# 01-Power.net
KiCad netlist of a schematic drawn in Altium Designer
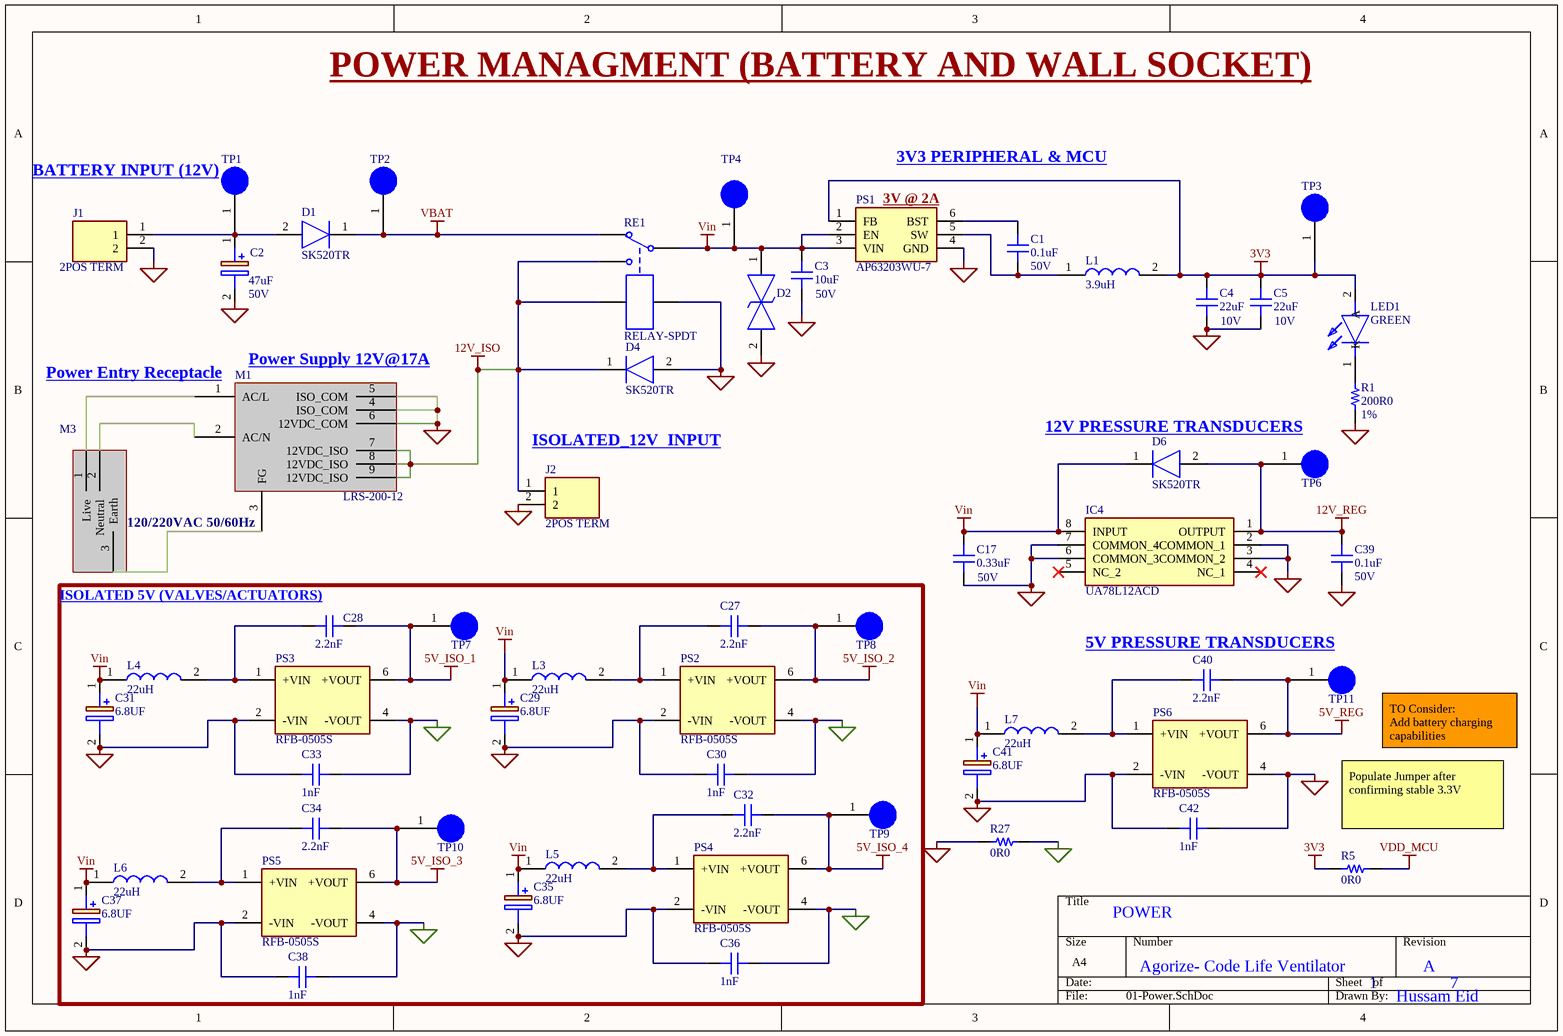
[diagram p0: 01-Power.SchDoc]

(export (version "E")
  (design (tool "Eeschema 10.0.6"))
  (components
    (comp (ref "C1")
      (value "0.1uF")
      (footprint "CAP 0603/1608")
      (description "CAP CER 0.1UF 50V X7R 0603")
      (fields (field (name "TOLERANCE") "20%") (field (name "VOLTAGE RATING") "50V"))
      (libsource (lib "Celestial Library Database") (part "Capacitor"))
    )
    (comp (ref "C2")
      (value "47uF")
      (footprint "SamacSys:EEE1HA470XP")
      (description "CAP ALUM 47UF 20% 50V SMD")
      (fields
        (field (name "TOLERANCE") "20%")
        (field (name "VOLTAGE RATING") "50V")
        (field (name "VOLTAGE") "50V")
      )
      (libsource (lib "*") (part "EEE-1HA470XP"))
    )
    (comp (ref "C3")
      (value "10uF")
      (footprint "CAP 1206/3216")
      (description "CAP CER 10UF 25V X7R 1206")
      (fields (field (name "TOLERANCE") "20%") (field (name "VOLTAGE RATING") "50V"))
      (libsource (lib "Celestial Library Database") (part "Capacitor"))
    )
    (comp (ref "C4")
      (value "22uF")
      (footprint "RES 0805/2012")
      (description "CAP CER 22UF 10V X5R 0805")
      (fields (field (name "VOLTAGE") "10V") (field (name "TOLERANCE") "20%"))
      (libsource (lib "Celestial Library Database") (part "Capacitor"))
    )
    (comp (ref "C5")
      (value "22uF")
      (footprint "RES 0805/2012")
      (description "CAP CER 22UF 10V X5R 0805")
      (fields (field (name "VOLTAGE") "10V") (field (name "TOLERANCE") "20%"))
      (libsource (lib "Celestial Library Database") (part "Capacitor"))
    )
    (comp (ref "C17")
      (value "0.33uF")
      (footprint "CAP 0603/1608")
      (description "CAP CER 0.33UF 50V X5R 0603")
      (fields (field (name "VOLTAGE RATING") "50V") (field (name "TOLERANCE") "10%"))
      (libsource (lib "Celestial Library Database") (part "Capacitor"))
    )
    (comp (ref "C27")
      (value "2.2nF")
      (footprint "CAP 0603/1608")
      (description "CAP CER 2.2nF 50V X7R 0603")
      (fields (field (name "TOLERANCE") "20%"))
      (libsource (lib "Celestial Library Database") (part "Capacitor"))
    )
    (comp (ref "C28")
      (value "2.2nF")
      (footprint "CAP 0603/1608")
      (description "CAP CER 2.2nF 50V X7R 0603")
      (fields (field (name "TOLERANCE") "20%"))
      (libsource (lib "Celestial Library Database") (part "Capacitor"))
    )
    (comp (ref "C29")
      (value "6.8UF")
      (footprint "CAPAE430X550N")
      (description "CAP 6.8 UF 20% 50 V")
      (fields (field (name "TOLERANCE") "20%"))
      (libsource (lib "Schlib1") (part "CAP_ELECTROLYTIC"))
    )
    (comp (ref "C30")
      (value "1nF")
      (footprint "CAP 0603/1608")
      (description "CAP CER 1nF 50V X7R 0603")
      (fields (field (name "TOLERANCE") "20%"))
      (libsource (lib "Celestial Library Database") (part "Capacitor"))
    )
    (comp (ref "C31")
      (value "6.8UF")
      (footprint "CAPAE430X550N")
      (description "CAP 6.8 UF 20% 50 V")
      (fields (field (name "TOLERANCE") "20%"))
      (libsource (lib "Schlib1") (part "CAP_ELECTROLYTIC"))
    )
    (comp (ref "C32")
      (value "2.2nF")
      (footprint "CAP 0603/1608")
      (description "CAP CER 2.2nF 50V X7R 0603")
      (fields (field (name "TOLERANCE") "20%"))
      (libsource (lib "Celestial Library Database") (part "Capacitor"))
    )
    (comp (ref "C33")
      (value "1nF")
      (footprint "CAP 0603/1608")
      (description "CAP CER 1nF 50V X7R 0603")
      (fields (field (name "TOLERANCE") "20%"))
      (libsource (lib "Celestial Library Database") (part "Capacitor"))
    )
    (comp (ref "C34")
      (value "2.2nF")
      (footprint "CAP 0603/1608")
      (description "CAP CER 2.2nF 50V X7R 0603")
      (fields (field (name "TOLERANCE") "20%"))
      (libsource (lib "Celestial Library Database") (part "Capacitor"))
    )
    (comp (ref "C35")
      (value "6.8UF")
      (footprint "CAPAE430X550N")
      (description "CAP 6.8 UF 20% 50 V")
      (fields (field (name "TOLERANCE") "20%"))
      (libsource (lib "Schlib1") (part "CAP_ELECTROLYTIC"))
    )
    (comp (ref "C36")
      (value "1nF")
      (footprint "CAP 0603/1608")
      (description "CAP CER 1nF 50V X7R 0603")
      (fields (field (name "TOLERANCE") "20%"))
      (libsource (lib "Celestial Library Database") (part "Capacitor"))
    )
    (comp (ref "C37")
      (value "6.8UF")
      (footprint "CAPAE430X550N")
      (description "CAP 6.8 UF 20% 50 V")
      (fields (field (name "TOLERANCE") "20%"))
      (libsource (lib "Schlib1") (part "CAP_ELECTROLYTIC"))
    )
    (comp (ref "C38")
      (value "1nF")
      (footprint "CAP 0603/1608")
      (description "CAP CER 1nF 50V X7R 0603")
      (fields (field (name "TOLERANCE") "20%"))
      (libsource (lib "Celestial Library Database") (part "Capacitor"))
    )
    (comp (ref "C39")
      (value "0.1uF")
      (footprint "CAP 0603/1608")
      (description "CAP CER 0.1UF 50V X7R 0603")
      (fields (field (name "TOLERANCE") "20%") (field (name "VOLTAGE RATING") "50V"))
      (libsource (lib "Celestial Library Database") (part "Capacitor"))
    )
    (comp (ref "C40")
      (value "2.2nF")
      (footprint "CAP 0603/1608")
      (description "CAP CER 2.2nF 50V X7R 0603")
      (fields (field (name "TOLERANCE") "20%"))
      (libsource (lib "Celestial Library Database") (part "Capacitor"))
    )
    (comp (ref "C41")
      (value "6.8UF")
      (footprint "CAPAE430X550N")
      (description "CAP 6.8 UF 20% 50 V")
      (fields (field (name "TOLERANCE") "20%"))
      (libsource (lib "Schlib1") (part "CAP_ELECTROLYTIC"))
    )
    (comp (ref "C42")
      (value "1nF")
      (footprint "CAP 0603/1608")
      (description "CAP CER 1nF 50V X7R 0603")
      (fields (field (name "TOLERANCE") "20%"))
      (libsource (lib "Celestial Library Database") (part "Capacitor"))
    )
    (comp (ref "D1")
      (value "SK520TR")
      (footprint "SamacSys:DIOM8060X295N")
      (description "DIODE SCHOTTKY 200V 5A SMC")
      (libsource (lib "*") (part "SK520TR"))
    )
    (comp (ref "D2")
      (value "DF2B26M4SL,L3F")
      (footprint "PcbLib1:TVS")
      (description "BI-DIRECTIONAL ESD PROTECTION DI")
      (libsource (lib "*") (part "1KSMB12CA"))
    )
    (comp (ref "D4")
      (value "SK520TR")
      (footprint "SamacSys:DIOM8060X295N")
      (description "DIODE SCHOTTKY 200V 5A SMC")
      (libsource (lib "*") (part "SK520TR"))
    )
    (comp (ref "D6")
      (value "SK520TR")
      (footprint "SamacSys:DIOM8060X295N")
      (description "DIODE SCHOTTKY 200V 5A SMC")
      (libsource (lib "*") (part "SK520TR"))
    )
    (comp (ref "IC4")
      (value "UA78L12ACD")
      (footprint "SamacSys:SOIC127P600X175-8N")
      (description "Linear Voltage Regulator IC  1 Output  100mA 8-SOIC")
      (fields (field (name "MOUSER PART NUMBER") "595-UA78L12ACD") (field (name "RS PART NUMBER") "6616727P"))
      (libsource (lib "*") (part "UA78L12ACD"))
    )
    (comp (ref "J1")
      (value "2POS TERM")
      (footprint "PcbLib1:SHDR2W110P0X500_1X2_1000X830X1140P")
      (description "TERM BLK 2POS SIDE ENTRY 5MM PCB")
      (fields (field (name "VOLTAGE") "300V"))
      (libsource (lib "*") (part "1935161"))
    )
    (comp (ref "J2")
      (value "2POS TERM")
      (footprint "PcbLib1:SHDR2W110P0X500_1X2_1000X830X1140P")
      (description "TERM BLK 2POS SIDE ENTRY 5MM PCB")
      (fields (field (name "VOLTAGE") "300V"))
      (libsource (lib "") (part "1935161_1"))
    )
    (comp (ref "L1")
      (value "3.9uH")
      (footprint "SamacSys:1255AY100MP3")
      (description "3.9µH Shielded Wirewound Inductor 4.2A 26.4mOhm Max Nonstandard")
      (fields (field (name "TOLERANCE") "30%"))
      (libsource (lib "*") (part "1255AY-3R9N=P3"))
    )
    (comp (ref "L3")
      (value "22uH")
      (footprint "SamacSys:1255AY100MP3")
      (description "Inductor Unshielded Wirewound  190mA 4.81Ohm Max 0805 (2012 Metric)")
      (fields (field (name "TOLERANCE") "20%"))
      (libsource (lib "*") (part "1255AY-3R9N=P3"))
    )
    (comp (ref "L4")
      (value "22uH")
      (footprint "SamacSys:1255AY100MP3")
      (description "Inductor Unshielded Wirewound  190mA 4.81Ohm Max 0805 (2012 Metric)")
      (fields (field (name "TOLERANCE") "20%"))
      (libsource (lib "*") (part "1255AY-3R9N=P3"))
    )
    (comp (ref "L5")
      (value "22uH")
      (footprint "SamacSys:1255AY100MP3")
      (description "Inductor Unshielded Wirewound  190mA 4.81Ohm Max 0805 (2012 Metric)")
      (fields (field (name "TOLERANCE") "20%"))
      (libsource (lib "*") (part "1255AY-3R9N=P3"))
    )
    (comp (ref "L6")
      (value "22uH")
      (footprint "SamacSys:1255AY100MP3")
      (description "Inductor Unshielded Wirewound  190mA 4.81Ohm Max 0805 (2012 Metric)")
      (fields (field (name "TOLERANCE") "20%"))
      (libsource (lib "*") (part "1255AY-3R9N=P3"))
    )
    (comp (ref "L7")
      (value "22uH")
      (footprint "SamacSys:1255AY100MP3")
      (description "Inductor Unshielded Wirewound  190mA 4.81Ohm Max 0805 (2012 Metric)")
      (fields (field (name "TOLERANCE") "20%"))
      (libsource (lib "*") (part "1255AY-3R9N=P3"))
    )
    (comp (ref "LED1")
      (value "GREEN")
      (footprint "SamacSys:150060GS73220")
      (description "LED GREEN CLEAR 0603 SMD")
      (libsource (lib "*") (part "150060GS73220"))
    )
    (comp (ref "M1")
      (value "12V 204W PS")
      (description "Enclosed AC DC Converters 1 Output 12V    17A 90 ~ 132 VAC, 180 ~ 264 VAC, 240 ~ 370 VDC Input")
      (fields (field (name "MANUFACTURER PART NUMBER 1") "LRS-200-12"))
      (libsource (lib "Schlib1") (part "12V 204W PS"))
    )
    (comp (ref "M3")
      (value "Power Entry Receptacle")
      (description "Power Entry Connector Receptacle, Male Blades IEC 320-C14 Panel Mount, Flange")
      (libsource (lib "Schlib1") (part "Power Entry Receptacle"))
    )
    (comp (ref "PS1")
      (value "AP63203WU-7")
      (footprint "SamacSys:SOT95P280X100-6N")
      (description "IC REG BUCK 3.3V 2A TSOT26")
      (libsource (lib "*") (part "AP63203WU-7"))
    )
    (comp (ref "PS2")
      (value "RFB-0505S")
      (footprint "SamacSys:RFB0505S")
      (description "DC DC CONVERTER 5V 1W")
      (fields (field (name "MOUSER PART NUMBER") "919-RFB-0505S") (field (name "RS PART NUMBER") "1855539P"))
      (libsource (lib "Schlib1") (part "RFB-0505S"))
    )
    (comp (ref "PS3")
      (value "RFB-0505S")
      (footprint "SamacSys:RFB0505S")
      (description "DC DC CONVERTER 5V 1W")
      (fields (field (name "MOUSER PART NUMBER") "919-RFB-0505S") (field (name "RS PART NUMBER") "1855539P"))
      (libsource (lib "Schlib1") (part "RFB-0505S"))
    )
    (comp (ref "PS4")
      (value "RFB-0505S")
      (footprint "SamacSys:RFB0505S")
      (description "DC DC CONVERTER 5V 1W")
      (fields (field (name "MOUSER PART NUMBER") "919-RFB-0505S") (field (name "RS PART NUMBER") "1855539P"))
      (libsource (lib "Schlib1") (part "RFB-0505S"))
    )
    (comp (ref "PS5")
      (value "RFB-0505S")
      (footprint "SamacSys:RFB0505S")
      (description "DC DC CONVERTER 5V 1W")
      (fields (field (name "MOUSER PART NUMBER") "919-RFB-0505S") (field (name "RS PART NUMBER") "1855539P"))
      (libsource (lib "Schlib1") (part "RFB-0505S"))
    )
    (comp (ref "PS6")
      (value "RFB-0505S")
      (footprint "SamacSys:RFB0505S")
      (description "DC DC CONVERTER 5V 1W")
      (fields (field (name "MOUSER PART NUMBER") "919-RFB-0505S") (field (name "RS PART NUMBER") "1855539P"))
      (libsource (lib "Schlib1") (part "RFB-0505S"))
    )
    (comp (ref "R1")
      (value "200R0")
      (footprint "RES 1206/3216")
      (description "RES SMD 10K OHM 1% 1/4W 1206")
      (fields (field (name "TOLERANCE") "1%"))
      (libsource (lib "Celestial Library Database") (part "Resistor"))
    )
    (comp (ref "R5")
      (value "0R0")
      (footprint "RES 0603/1608")
      (description "RES SMD 0 OHM JUMPER 1/10W 0603")
      (fields (field (name "TOLERANCE") "0%"))
      (libsource (lib "Celestial Library Database") (part "Resistor"))
    )
    (comp (ref "R27")
      (value "0R0")
      (footprint "RES 0603/1608")
      (description "RES SMD 0 OHM JUMPER 1/10W 0603")
      (fields (field (name "TOLERANCE") "0%"))
      (libsource (lib "Celestial Library Database") (part "Resistor"))
    )
    (comp (ref "RE1")
      (value "RELAY-SPDT")
      (footprint "T9GV5L145")
      (description "RELAY GEN PURPOSE SPDT 20A 12V")
      (libsource (lib "Schlib1") (part "RELAY-SPDT"))
    )
    (comp (ref "TP1")
      (value "TP")
      (footprint "TP")
      (description "Test Point")
      (libsource (lib "Schlib1") (part "TP"))
    )
    (comp (ref "TP2")
      (value "TP")
      (footprint "TP")
      (description "Test Point")
      (libsource (lib "Schlib1") (part "TP"))
    )
    (comp (ref "TP3")
      (value "TP")
      (footprint "TP")
      (description "Test Point")
      (libsource (lib "Schlib1") (part "TP"))
    )
    (comp (ref "TP4")
      (value "TP")
      (footprint "TP")
      (description "Test Point")
      (libsource (lib "Schlib1") (part "TP"))
    )
    (comp (ref "TP6")
      (value "TP")
      (footprint "TP")
      (description "Test Point")
      (libsource (lib "Schlib1") (part "TP"))
    )
    (comp (ref "TP7")
      (value "TP")
      (footprint "TP")
      (description "Test Point")
      (libsource (lib "Schlib1") (part "TP"))
    )
    (comp (ref "TP8")
      (value "TP")
      (footprint "TP")
      (description "Test Point")
      (libsource (lib "Schlib1") (part "TP"))
    )
    (comp (ref "TP9")
      (value "TP")
      (footprint "TP")
      (description "Test Point")
      (libsource (lib "Schlib1") (part "TP"))
    )
    (comp (ref "TP10")
      (value "TP")
      (footprint "TP")
      (description "Test Point")
      (libsource (lib "Schlib1") (part "TP"))
    )
    (comp (ref "TP11")
      (value "TP")
      (footprint "TP")
      (description "Test Point")
      (libsource (lib "Schlib1") (part "TP"))
    )
  )
  (nets
    (net (code "1") (name "3V3") (class "Default")
      (node (ref "C4") (pin "2") (pinfunction "2_2") (pintype "passive"))
      (node (ref "C5") (pin "2") (pinfunction "2_2") (pintype "passive"))
      (node (ref "L1") (pin "2") (pinfunction "2_2") (pintype "passive"))
      (node (ref "LED1") (pin "2") (pinfunction "A_2") (pintype "passive"))
      (node (ref "PS1") (pin "1") (pinfunction "FB_1") (pintype "passive"))
      (node (ref "R5") (pin "1") (pinfunction "1_1") (pintype "passive"))
      (node (ref "TP3") (pin "1") (pinfunction "1_1") (pintype "passive"))
    )
    (net (code "2") (name "5V_ISO_1") (class "Default")
      (node (ref "C28") (pin "2") (pinfunction "2_2") (pintype "passive"))
      (node (ref "PS3") (pin "6") (pinfunction "+VOUT_6") (pintype "passive"))
      (node (ref "TP7") (pin "1") (pinfunction "1_1") (pintype "passive"))
    )
    (net (code "3") (name "5V_ISO_2") (class "Default")
      (node (ref "C27") (pin "2") (pinfunction "2_2") (pintype "passive"))
      (node (ref "PS2") (pin "6") (pinfunction "+VOUT_6") (pintype "passive"))
      (node (ref "TP8") (pin "1") (pinfunction "1_1") (pintype "passive"))
    )
    (net (code "4") (name "5V_ISO_3") (class "Default")
      (node (ref "C34") (pin "2") (pinfunction "2_2") (pintype "passive"))
      (node (ref "PS5") (pin "6") (pinfunction "+VOUT_6") (pintype "passive"))
      (node (ref "TP10") (pin "1") (pinfunction "1_1") (pintype "passive"))
    )
    (net (code "5") (name "5V_ISO_4") (class "Default")
      (node (ref "C32") (pin "2") (pinfunction "2_2") (pintype "passive"))
      (node (ref "PS4") (pin "6") (pinfunction "+VOUT_6") (pintype "passive"))
      (node (ref "TP9") (pin "1") (pinfunction "1_1") (pintype "passive"))
    )
    (net (code "6") (name "5V_REG") (class "Default")
      (node (ref "C40") (pin "2") (pinfunction "2_2") (pintype "passive"))
      (node (ref "PS6") (pin "6") (pinfunction "+VOUT_6") (pintype "passive"))
      (node (ref "TP11") (pin "1") (pinfunction "1_1") (pintype "passive"))
    )
    (net (code "7") (name "12V_ISO") (class "Default")
      (node (ref "D4") (pin "1") (pinfunction "K_1") (pintype "passive"))
      (node (ref "J2") (pin "1") (pinfunction "1_1") (pintype "passive"))
      (node (ref "M1") (pin "7") (pinfunction "12VDC_ISO_7") (pintype "passive"))
      (node (ref "M1") (pin "8") (pinfunction "12VDC_ISO_8") (pintype "passive"))
      (node (ref "M1") (pin "9") (pinfunction "12VDC_ISO_9") (pintype "passive"))
      (node (ref "RE1") (pin "3") (pinfunction "3_3") (pintype "passive"))
      (node (ref "RE1") (pin "4") (pinfunction "4_4") (pintype "passive"))
    )
    (net (code "8") (name "12V_REG") (class "Default")
      (node (ref "C39") (pin "1") (pinfunction "1_1") (pintype "passive"))
      (node (ref "D6") (pin "2") (pinfunction "A_2") (pintype "passive"))
      (node (ref "IC4") (pin "1") (pinfunction "OUTPUT_1") (pintype "passive"))
      (node (ref "TP6") (pin "1") (pinfunction "1_1") (pintype "passive"))
    )
    (net (code "9") (name "COM") (class "Default")
      (node (ref "C17") (pin "2") (pinfunction "2_2") (pintype "passive"))
      (node (ref "C2") (pin "2") (pinfunction "-_2") (pintype "passive"))
      (node (ref "C29") (pin "2") (pinfunction "-_2") (pintype "passive"))
      (node (ref "C3") (pin "1") (pinfunction "1_1") (pintype "passive"))
      (node (ref "C30") (pin "1") (pinfunction "1_1") (pintype "passive"))
      (node (ref "C31") (pin "2") (pinfunction "-_2") (pintype "passive"))
      (node (ref "C33") (pin "1") (pinfunction "1_1") (pintype "passive"))
      (node (ref "C35") (pin "2") (pinfunction "-_2") (pintype "passive"))
      (node (ref "C36") (pin "1") (pinfunction "1_1") (pintype "passive"))
      (node (ref "C37") (pin "2") (pinfunction "-_2") (pintype "passive"))
      (node (ref "C38") (pin "1") (pinfunction "1_1") (pintype "passive"))
      (node (ref "C39") (pin "2") (pinfunction "2_2") (pintype "passive"))
      (node (ref "C4") (pin "1") (pinfunction "1_1") (pintype "passive"))
      (node (ref "C41") (pin "2") (pinfunction "-_2") (pintype "passive"))
      (node (ref "C42") (pin "1") (pinfunction "1_1") (pintype "passive"))
      (node (ref "C42") (pin "2") (pinfunction "2_2") (pintype "passive"))
      (node (ref "C5") (pin "1") (pinfunction "1_1") (pintype "passive"))
      (node (ref "D2") (pin "2") (pinfunction "2_2") (pintype "passive"))
      (node (ref "D4") (pin "2") (pinfunction "A_2") (pintype "passive"))
      (node (ref "IC4") (pin "2") (pinfunction "COMMON_1_2") (pintype "passive"))
      (node (ref "IC4") (pin "3") (pinfunction "COMMON_2_3") (pintype "passive"))
      (node (ref "IC4") (pin "6") (pinfunction "COMMON_3_6") (pintype "passive"))
      (node (ref "IC4") (pin "7") (pinfunction "COMMON_4_7") (pintype "passive"))
      (node (ref "J1") (pin "2") (pinfunction "2_2") (pintype "passive"))
      (node (ref "J2") (pin "2") (pinfunction "2_2") (pintype "passive"))
      (node (ref "M1") (pin "4") (pinfunction "ISO_COM_4") (pintype "passive"))
      (node (ref "M1") (pin "5") (pinfunction "ISO_COM_5") (pintype "passive"))
      (node (ref "M1") (pin "6") (pinfunction "12VDC_COM_6") (pintype "passive"))
      (node (ref "PS1") (pin "4") (pinfunction "GND_4") (pintype "power_in"))
      (node (ref "PS2") (pin "2") (pinfunction "-VIN_2") (pintype "passive"))
      (node (ref "PS3") (pin "2") (pinfunction "-VIN_2") (pintype "passive"))
      (node (ref "PS4") (pin "2") (pinfunction "-VIN_2") (pintype "passive"))
      (node (ref "PS5") (pin "2") (pinfunction "-VIN_2") (pintype "passive"))
      (node (ref "PS6") (pin "2") (pinfunction "-VIN_2") (pintype "passive"))
      (node (ref "PS6") (pin "4") (pinfunction "-VOUT_4") (pintype "passive"))
      (node (ref "R1") (pin "1") (pinfunction "1_1") (pintype "passive"))
      (node (ref "R27") (pin "1") (pinfunction "1_1") (pintype "passive"))
      (node (ref "RE1") (pin "2") (pinfunction "2_2") (pintype "passive"))
    )
    (net (code "10") (name "COM_ISO") (class "Default")
      (node (ref "C30") (pin "2") (pinfunction "2_2") (pintype "passive"))
      (node (ref "C33") (pin "2") (pinfunction "2_2") (pintype "passive"))
      (node (ref "C36") (pin "2") (pinfunction "2_2") (pintype "passive"))
      (node (ref "C38") (pin "2") (pinfunction "2_2") (pintype "passive"))
      (node (ref "PS2") (pin "4") (pinfunction "-VOUT_4") (pintype "passive"))
      (node (ref "PS3") (pin "4") (pinfunction "-VOUT_4") (pintype "passive"))
      (node (ref "PS4") (pin "4") (pinfunction "-VOUT_4") (pintype "passive"))
      (node (ref "PS5") (pin "4") (pinfunction "-VOUT_4") (pintype "passive"))
      (node (ref "R27") (pin "2") (pinfunction "2_2") (pintype "passive"))
    )
    (net (code "11") (name "Net-(C2-+)") (class "Default")
      (node (ref "C2") (pin "1") (pinfunction "+_1") (pintype "passive"))
      (node (ref "D1") (pin "2") (pinfunction "A_2") (pintype "passive"))
      (node (ref "J1") (pin "1") (pinfunction "1_1") (pintype "passive"))
      (node (ref "TP1") (pin "1") (pinfunction "1_1") (pintype "passive"))
    )
    (net (code "12") (name "Net-(LED1-K)") (class "Default")
      (node (ref "LED1") (pin "1") (pinfunction "K_1") (pintype "passive"))
      (node (ref "R1") (pin "2") (pinfunction "2_2") (pintype "passive"))
    )
    (net (code "13") (name "Net-(M1-AC{slash}L)") (class "Default")
      (node (ref "M1") (pin "1") (pinfunction "AC/L_1") (pintype "passive"))
      (node (ref "M3") (pin "1") (pinfunction "Live_1") (pintype "passive"))
    )
    (net (code "14") (name "Net-(M1-AC{slash}N)") (class "Default")
      (node (ref "M1") (pin "2") (pinfunction "AC/N_2") (pintype "passive"))
      (node (ref "M3") (pin "2") (pinfunction "Neutral_2") (pintype "passive"))
    )
    (net (code "15") (name "Net-(M1-FG)") (class "Default")
      (node (ref "M1") (pin "3") (pinfunction "FG_3") (pintype "passive"))
      (node (ref "M3") (pin "3") (pinfunction "Earth_3") (pintype "passive"))
    )
    (net (code "16") (name "Net-(PS1-BST)") (class "Default")
      (node (ref "C1") (pin "1") (pinfunction "1_1") (pintype "passive"))
      (node (ref "PS1") (pin "6") (pinfunction "BST_6") (pintype "passive"))
    )
    (net (code "17") (name "Net-(PS1-SW)") (class "Default")
      (node (ref "C1") (pin "2") (pinfunction "2_2") (pintype "passive"))
      (node (ref "L1") (pin "1") (pinfunction "1_1") (pintype "passive"))
      (node (ref "PS1") (pin "5") (pinfunction "SW_5") (pintype "passive"))
    )
    (net (code "18") (name "Net-(PS2-+VIN)") (class "Default")
      (node (ref "C27") (pin "1") (pinfunction "1_1") (pintype "passive"))
      (node (ref "L3") (pin "2") (pinfunction "2_2") (pintype "passive"))
      (node (ref "PS2") (pin "1") (pinfunction "+VIN_1") (pintype "passive"))
    )
    (net (code "19") (name "Net-(PS3-+VIN)") (class "Default")
      (node (ref "C28") (pin "1") (pinfunction "1_1") (pintype "passive"))
      (node (ref "L4") (pin "2") (pinfunction "2_2") (pintype "passive"))
      (node (ref "PS3") (pin "1") (pinfunction "+VIN_1") (pintype "passive"))
    )
    (net (code "20") (name "Net-(PS4-+VIN)") (class "Default")
      (node (ref "C32") (pin "1") (pinfunction "1_1") (pintype "passive"))
      (node (ref "L5") (pin "2") (pinfunction "2_2") (pintype "passive"))
      (node (ref "PS4") (pin "1") (pinfunction "+VIN_1") (pintype "passive"))
    )
    (net (code "21") (name "Net-(PS5-+VIN)") (class "Default")
      (node (ref "C34") (pin "1") (pinfunction "1_1") (pintype "passive"))
      (node (ref "L6") (pin "2") (pinfunction "2_2") (pintype "passive"))
      (node (ref "PS5") (pin "1") (pinfunction "+VIN_1") (pintype "passive"))
    )
    (net (code "22") (name "Net-(PS6-+VIN)") (class "Default")
      (node (ref "C40") (pin "1") (pinfunction "1_1") (pintype "passive"))
      (node (ref "L7") (pin "2") (pinfunction "2_2") (pintype "passive"))
      (node (ref "PS6") (pin "1") (pinfunction "+VIN_1") (pintype "passive"))
    )
    (net (code "23") (name "VBAT") (class "Default")
      (node (ref "D1") (pin "1") (pinfunction "K_1") (pintype "passive"))
      (node (ref "RE1") (pin "5") (pinfunction "5_5") (pintype "passive"))
      (node (ref "TP2") (pin "1") (pinfunction "1_1") (pintype "passive"))
    )
    (net (code "24") (name "VDD_MCU") (class "Default")
      (node (ref "R5") (pin "2") (pinfunction "2_2") (pintype "passive"))
    )
    (net (code "25") (name "Vin") (class "Default")
      (node (ref "C17") (pin "1") (pinfunction "1_1") (pintype "passive"))
      (node (ref "C29") (pin "1") (pinfunction "+_1") (pintype "passive"))
      (node (ref "C3") (pin "2") (pinfunction "2_2") (pintype "passive"))
      (node (ref "C31") (pin "1") (pinfunction "+_1") (pintype "passive"))
      (node (ref "C35") (pin "1") (pinfunction "+_1") (pintype "passive"))
      (node (ref "C37") (pin "1") (pinfunction "+_1") (pintype "passive"))
      (node (ref "C41") (pin "1") (pinfunction "+_1") (pintype "passive"))
      (node (ref "D2") (pin "1") (pinfunction "1_1") (pintype "passive"))
      (node (ref "D6") (pin "1") (pinfunction "K_1") (pintype "passive"))
      (node (ref "IC4") (pin "8") (pinfunction "INPUT_8") (pintype "passive"))
      (node (ref "L3") (pin "1") (pinfunction "1_1") (pintype "passive"))
      (node (ref "L4") (pin "1") (pinfunction "1_1") (pintype "passive"))
      (node (ref "L5") (pin "1") (pinfunction "1_1") (pintype "passive"))
      (node (ref "L6") (pin "1") (pinfunction "1_1") (pintype "passive"))
      (node (ref "L7") (pin "1") (pinfunction "1_1") (pintype "passive"))
      (node (ref "PS1") (pin "2") (pinfunction "EN_2") (pintype "passive"))
      (node (ref "PS1") (pin "3") (pinfunction "VIN_3") (pintype "power_in"))
      (node (ref "RE1") (pin "1") (pinfunction "1_1") (pintype "passive"))
      (node (ref "TP4") (pin "1") (pinfunction "1_1") (pintype "passive"))
    )
    (net (code "26") (name "unconnected-(IC4-NC_1-Pad4)") (class "Default")
      (node (ref "IC4") (pin "4") (pinfunction "NC_1_4") (pintype "passive+no_connect"))
    )
    (net (code "27") (name "unconnected-(IC4-NC_2-Pad5)") (class "Default")
      (node (ref "IC4") (pin "5") (pinfunction "NC_2_5") (pintype "passive+no_connect"))
    )
  )
)
